# NixieFriday.net
KiCad netlist of a schematic drawn in Altium Designer
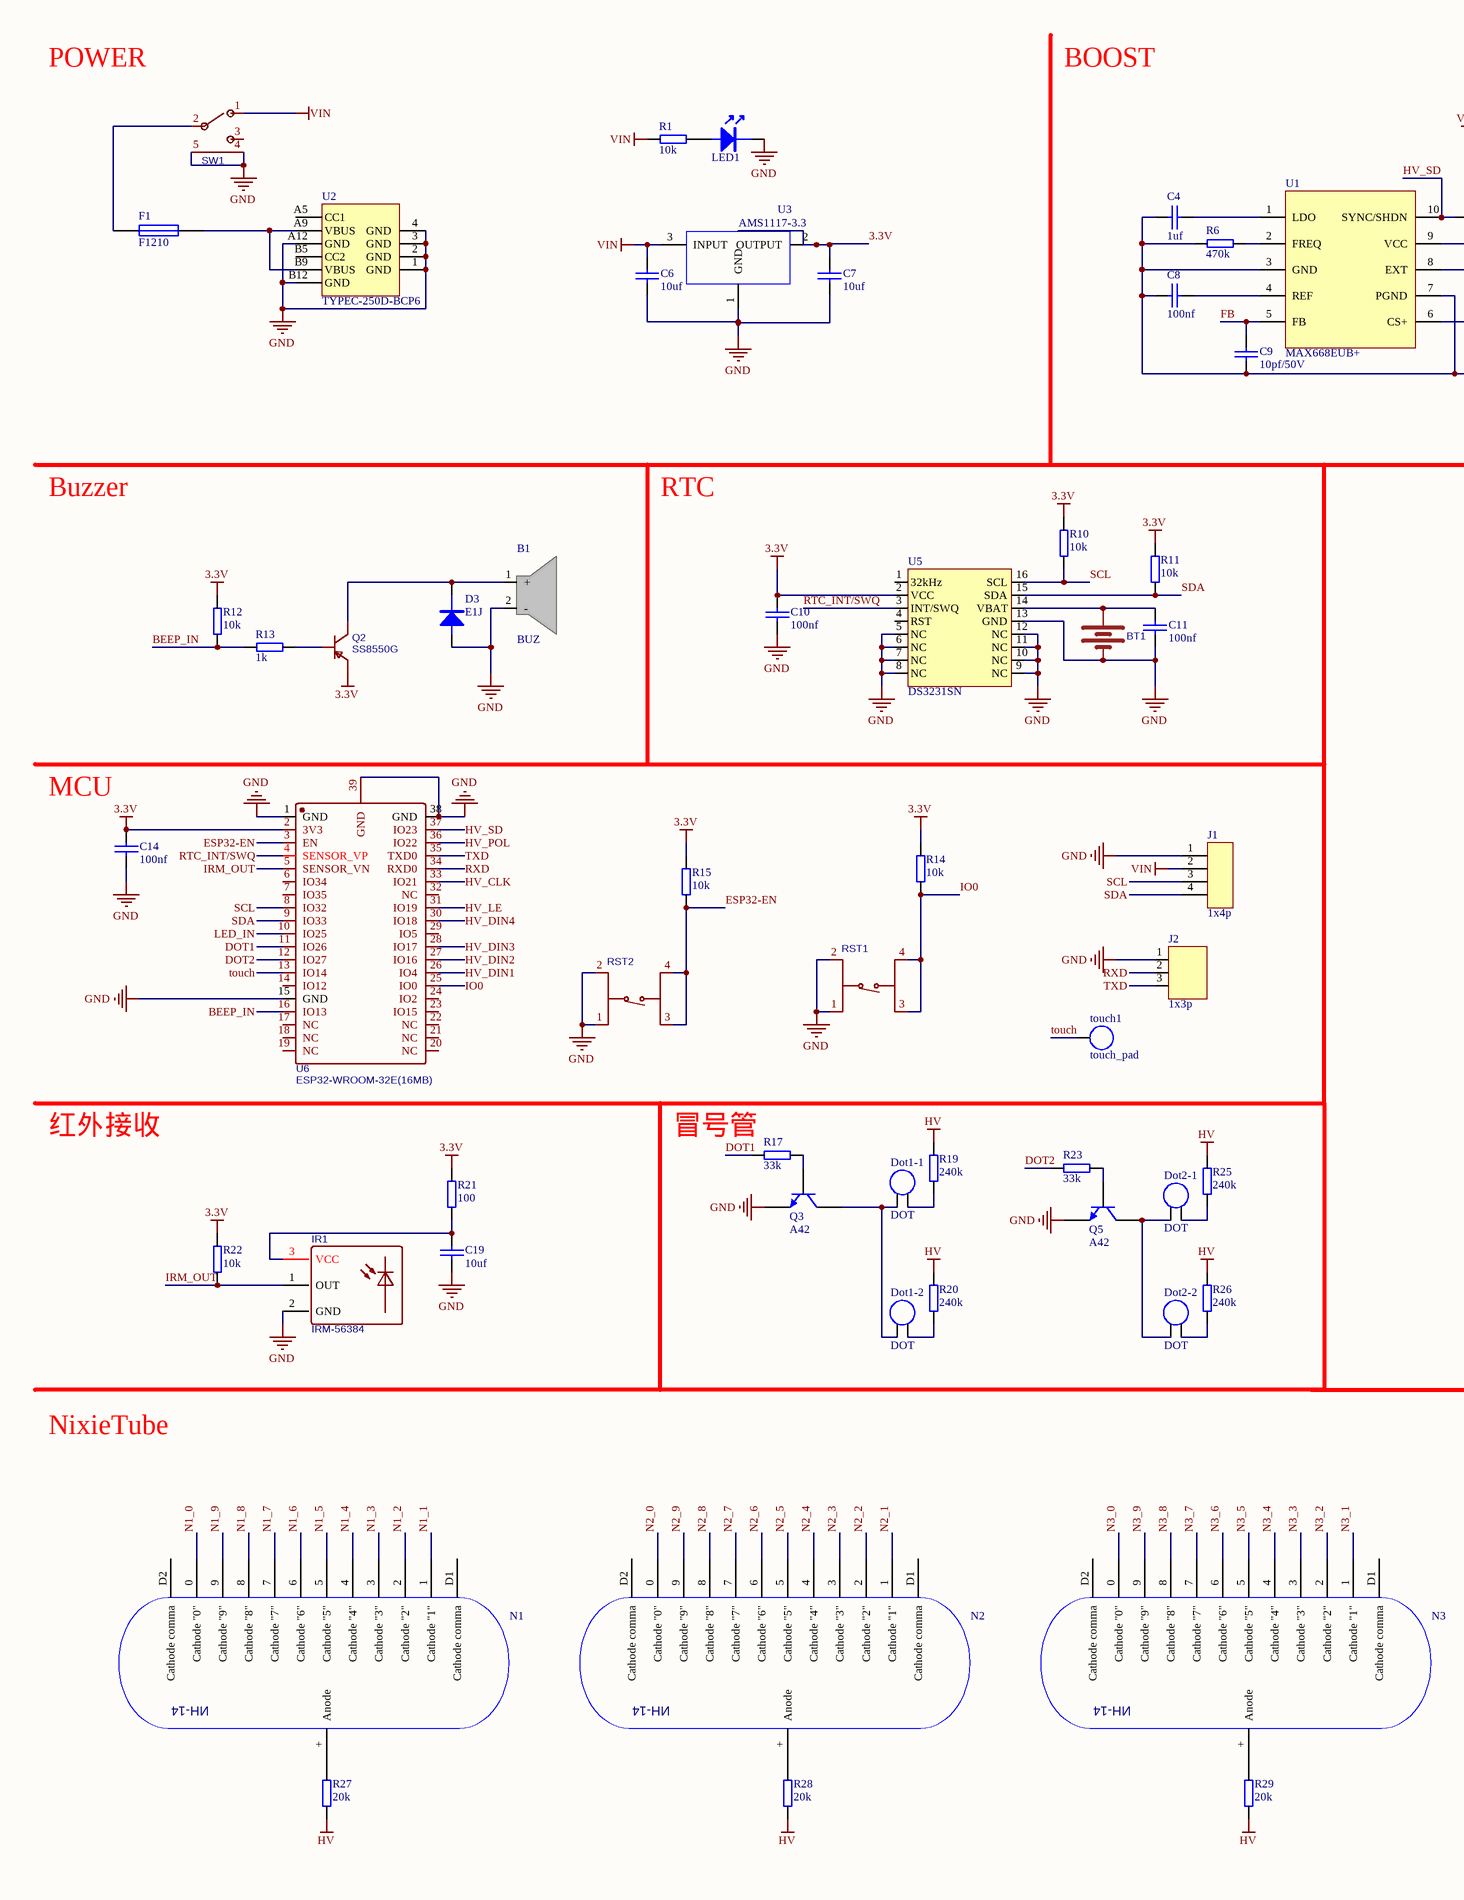
[diagram p0: NixieFriday.SchDoc, left]
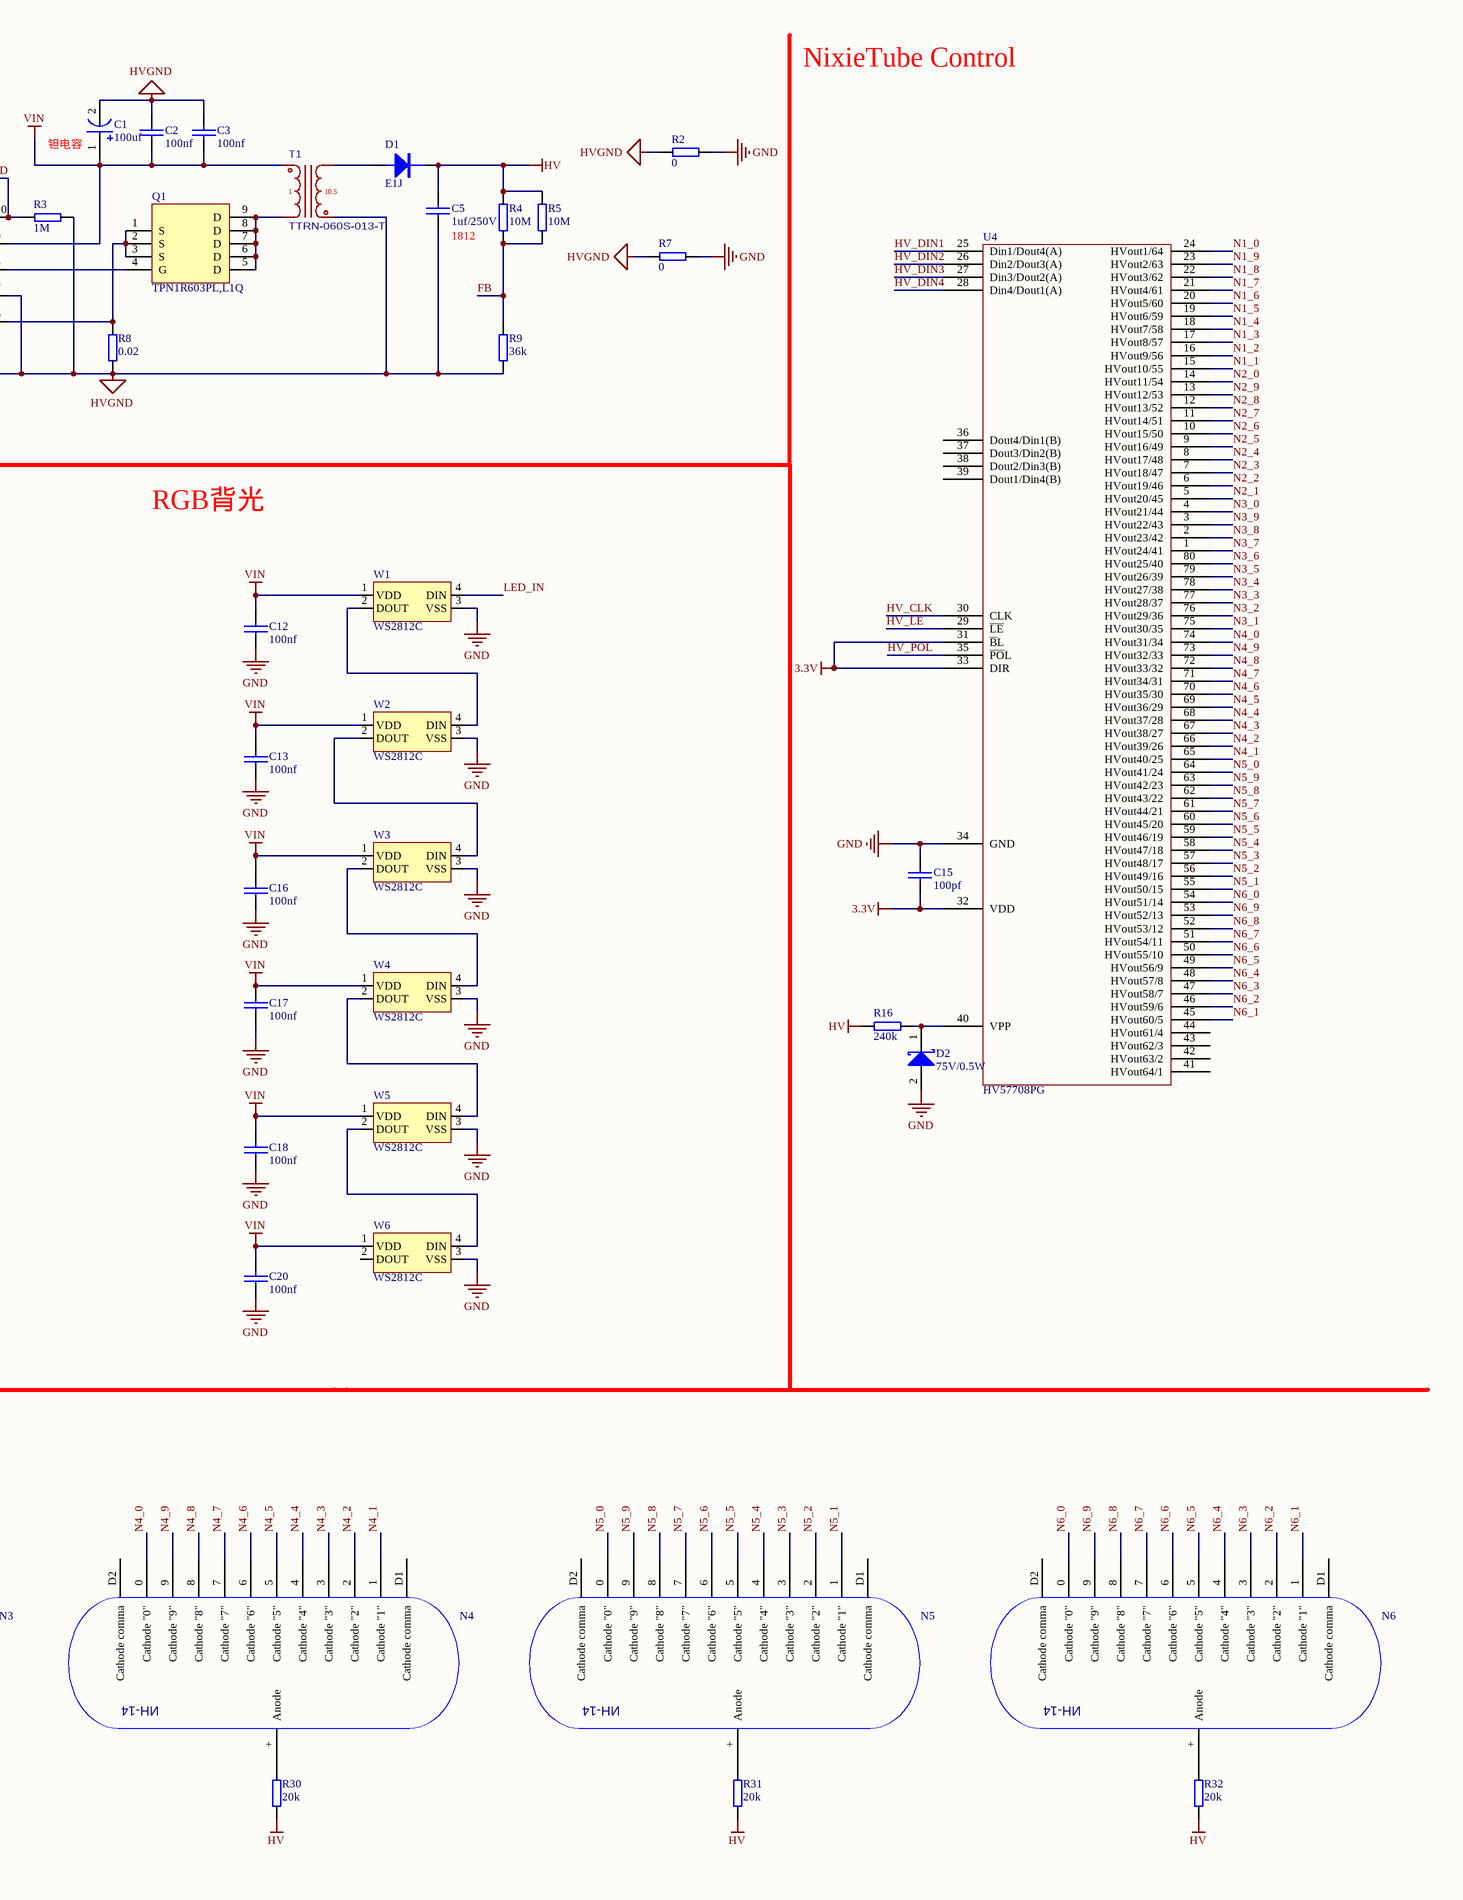
[diagram p1: NixieFriday.SchDoc, right]

(export (version "E")
  (design (tool "Eeschema 10.0.6"))
  (components
    (comp (ref "B1")
      (value "BUZ")
      (footprint "BUZ-SMD_4P-L8.5-W8.5-TL")
      (description "蜂鸣器")
      (libsource (lib "NixieFriday") (part "BUZ"))
    )
    (comp (ref "BT1")
      (value "BS-12-B3AA003")
      (footprint "BAT-SMD_BS-12-B3AA011")
      (description "纽扣电池")
      (fields (field (name "BOM_SUPPLIER PART") "C964723") (field (name "CONTRIBUTOR") "LCSC"))
      (libsource (lib "NixieFriday") (part "BS-12-B3AA003"))
    )
    (comp (ref "C1")
      (value "100uf")
      (footprint "CAP-SMD_L3.2-W1.6-RD")
      (description "极性电容")
      (libsource (lib "NixieFriday") (part "Cap_pol"))
    )
    (comp (ref "C2")
      (value "100nf")
      (footprint "C0603")
      (description "电容")
      (libsource (lib "NixieFriday") (part "Cap"))
    )
    (comp (ref "C3")
      (value "100nf")
      (footprint "C0603")
      (description "电容")
      (libsource (lib "NixieFriday") (part "Cap"))
    )
    (comp (ref "C4")
      (value "1uf")
      (footprint "C0603")
      (description "电容")
      (libsource (lib "NixieFriday") (part "Cap"))
    )
    (comp (ref "C5")
      (value "1uf/250V")
      (footprint "C1812")
      (description "电容")
      (libsource (lib "NixieFriday") (part "Cap"))
    )
    (comp (ref "C6")
      (value "10uf")
      (footprint "C0603")
      (description "电容")
      (libsource (lib "NixieFriday") (part "Cap"))
    )
    (comp (ref "C7")
      (value "10uf")
      (footprint "C0603")
      (description "电容")
      (libsource (lib "NixieFriday") (part "Cap"))
    )
    (comp (ref "C8")
      (value "100nf")
      (footprint "C0603")
      (description "电容")
      (libsource (lib "NixieFriday") (part "Cap"))
    )
    (comp (ref "C9")
      (value "10pf/50V")
      (footprint "C0603")
      (description "电容")
      (libsource (lib "NixieFriday") (part "Cap"))
    )
    (comp (ref "C10")
      (value "100nf")
      (footprint "C0603")
      (description "电容")
      (libsource (lib "NixieFriday") (part "Cap"))
    )
    (comp (ref "C11")
      (value "100nf")
      (footprint "C0603")
      (description "电容")
      (libsource (lib "NixieFriday") (part "Cap"))
    )
    (comp (ref "C12")
      (value "100nf")
      (footprint "C0603")
      (description "电容")
      (libsource (lib "NixieFriday") (part "Cap"))
    )
    (comp (ref "C13")
      (value "100nf")
      (footprint "C0603")
      (description "电容")
      (libsource (lib "NixieFriday") (part "Cap"))
    )
    (comp (ref "C14")
      (value "100nf")
      (footprint "C0603")
      (description "电容")
      (libsource (lib "NixieFriday") (part "Cap"))
    )
    (comp (ref "C15")
      (value "100pf")
      (footprint "C0603")
      (description "电容")
      (libsource (lib "NixieFriday") (part "Cap"))
    )
    (comp (ref "C16")
      (value "100nf")
      (footprint "C0603")
      (description "电容")
      (libsource (lib "NixieFriday") (part "Cap"))
    )
    (comp (ref "C17")
      (value "100nf")
      (footprint "C0603")
      (description "电容")
      (libsource (lib "NixieFriday") (part "Cap"))
    )
    (comp (ref "C18")
      (value "100nf")
      (footprint "C0603")
      (description "电容")
      (libsource (lib "NixieFriday") (part "Cap"))
    )
    (comp (ref "C19")
      (value "10uf")
      (footprint "C0603")
      (description "电容")
      (libsource (lib "NixieFriday") (part "Cap"))
    )
    (comp (ref "C20")
      (value "100nf")
      (footprint "C0603")
      (description "电容")
      (libsource (lib "NixieFriday") (part "Cap"))
    )
    (comp (ref "D1")
      (value "E1J")
      (footprint "SOD-123FL_L2.7-W1.8-LS3.8-RD")
      (libsource (lib "NixieFriday") (part "E1J"))
    )
    (comp (ref "D2")
      (value "75V/0.5W")
      (footprint "75V二极管")
      (description "Schottky Rectifier")
      (fields (field (name "PUBLISHER") "Altium Limited"))
      (libsource (lib "NixieFriday") (part "Diode 10TQ040"))
    )
    (comp (ref "D3")
      (value "E1J")
      (footprint "SOD-123FL_L2.7-W1.8-LS3.8-RD")
      (libsource (lib "NixieFriday") (part "E1J"))
    )
    (comp (ref "Dot1-1")
      (value "DOT")
      (footprint "Neon")
      (description "4x10mm氖泡")
      (libsource (lib "NixieFriday") (part "DOT"))
    )
    (comp (ref "Dot1-2")
      (value "DOT")
      (footprint "Neon")
      (description "4x10mm氖泡")
      (libsource (lib "NixieFriday") (part "DOT"))
    )
    (comp (ref "Dot2-1")
      (value "DOT")
      (footprint "Neon")
      (description "4x10mm氖泡")
      (libsource (lib "NixieFriday") (part "DOT"))
    )
    (comp (ref "Dot2-2")
      (value "DOT")
      (footprint "Neon")
      (description "4x10mm氖泡")
      (libsource (lib "NixieFriday") (part "DOT"))
    )
    (comp (ref "F1")
      (value "F1210")
      (footprint "F1210")
      (fields (field (name "PUBLISHER") "Altium Limited"))
      (libsource (lib "NixieFriday") (part "F1210"))
    )
    (comp (ref "IR1")
      (value "IRM-56384")
      (footprint "OPTO-TH_IRM-56384")
      (description "红外接收管")
      (fields (field (name "BOM_SUPPLIER PART") "C72048"))
      (libsource (lib "NixieFriday") (part "IRM-56384"))
    )
    (comp (ref "J1")
      (value "1x4p")
      (footprint "1x4p_2.54_弯")
      (description "2.54mm")
      (libsource (lib "NixieFriday") (part "1x4p"))
    )
    (comp (ref "J2") (value "1x3p") (footprint "1x3p") (libsource (lib "NixieFriday") (part "1x3p")))
    (comp (ref "LED1")
      (value "LED")
      (footprint "LED0603")
      (description "LED发光管")
      (libsource (lib "pwoer_test") (part "LED"))
    )
    (comp (ref "N1") (value "ИН-14") (footprint "NH_14_PIN") (libsource (lib "NixieFriday") (part "ИН-14")))
    (comp (ref "N2") (value "ИН-14") (footprint "NH_14_PIN") (libsource (lib "NixieFriday") (part "ИН-14")))
    (comp (ref "N3") (value "ИН-14") (footprint "NH_14_PIN") (libsource (lib "NixieFriday") (part "ИН-14")))
    (comp (ref "N4") (value "ИН-14") (footprint "NH_14_PIN") (libsource (lib "NixieFriday") (part "ИН-14")))
    (comp (ref "N5") (value "ИН-14") (footprint "NH_14_PIN") (libsource (lib "NixieFriday") (part "ИН-14")))
    (comp (ref "N6") (value "ИН-14") (footprint "NH_14_PIN") (libsource (lib "NixieFriday") (part "ИН-14")))
    (comp (ref "Q1")
      (value "TPN1R603PL,L1Q")
      (footprint "PG-TSDSON-8_L3.3-W3.3-P0.65-BL")
      (libsource (lib "NixieFriday") (part "TPN1R603PL,L1Q"))
    )
    (comp (ref "Q2")
      (value "SS8550G")
      (footprint "ss8550g")
      (fields (field (name "BOM_SUPPLIER PART") "C380931") (field (name "CONTRIBUTOR") "LCSC"))
      (libsource (lib "NixieFriday") (part "SS8550G"))
    )
    (comp (ref "Q3")
      (value "A42")
      (footprint "SOT-23-3")
      (description "NPN General Purpose Amplifier")
      (fields (field (name "PUBLISHER") "Altium Limited"))
      (libsource (lib "NixieFriday") (part "2N3904"))
    )
    (comp (ref "Q5")
      (value "A42")
      (footprint "SOT-23-3")
      (description "NPN General Purpose Amplifier")
      (fields (field (name "PUBLISHER") "Altium Limited"))
      (libsource (lib "NixieFriday") (part "2N3904"))
    )
    (comp (ref "R1")
      (value "10k")
      (footprint "R0603")
      (description "电阻")
      (libsource (lib "NixieFriday") (part "R"))
    )
    (comp (ref "R2")
      (value "0")
      (footprint "R0805")
      (description "电阻")
      (libsource (lib "NixieFriday") (part "R"))
    )
    (comp (ref "R3")
      (value "1M")
      (footprint "R0603")
      (description "电阻")
      (libsource (lib "NixieFriday") (part "R"))
    )
    (comp (ref "R4")
      (value "10M")
      (footprint "R0805")
      (description "电阻")
      (libsource (lib "NixieFriday") (part "R"))
    )
    (comp (ref "R5")
      (value "10M")
      (footprint "R0805")
      (description "电阻")
      (libsource (lib "NixieFriday") (part "R"))
    )
    (comp (ref "R6")
      (value "470k")
      (footprint "R0603")
      (description "电阻")
      (libsource (lib "NixieFriday") (part "R"))
    )
    (comp (ref "R7")
      (value "0")
      (footprint "R0805")
      (description "电阻")
      (libsource (lib "NixieFriday") (part "R"))
    )
    (comp (ref "R8")
      (value "0.02")
      (footprint "R0805")
      (description "电阻")
      (libsource (lib "NixieFriday") (part "R"))
    )
    (comp (ref "R9")
      (value "36k")
      (footprint "R0805")
      (description "电阻")
      (libsource (lib "NixieFriday") (part "R"))
    )
    (comp (ref "R10")
      (value "10k")
      (footprint "R0603")
      (description "电阻")
      (libsource (lib "NixieFriday") (part "R"))
    )
    (comp (ref "R11")
      (value "10k")
      (footprint "R0603")
      (description "电阻")
      (libsource (lib "NixieFriday") (part "R"))
    )
    (comp (ref "R12")
      (value "10k")
      (footprint "R0603")
      (description "电阻")
      (libsource (lib "NixieFriday") (part "R"))
    )
    (comp (ref "R13")
      (value "1k")
      (footprint "R0603")
      (description "电阻")
      (libsource (lib "NixieFriday") (part "R"))
    )
    (comp (ref "R14")
      (value "10k")
      (footprint "R0603")
      (description "电阻")
      (libsource (lib "NixieFriday") (part "R"))
    )
    (comp (ref "R15")
      (value "10k")
      (footprint "R0603")
      (description "电阻")
      (libsource (lib "NixieFriday") (part "R"))
    )
    (comp (ref "R16")
      (value "240k")
      (footprint "R0805")
      (description "电阻")
      (libsource (lib "NixieFriday") (part "R"))
    )
    (comp (ref "R17")
      (value "33k")
      (footprint "R0603")
      (description "电阻")
      (libsource (lib "NixieFriday") (part "R"))
    )
    (comp (ref "R19")
      (value "240k")
      (footprint "R0805")
      (description "电阻")
      (libsource (lib "NixieFriday") (part "R"))
    )
    (comp (ref "R20")
      (value "240k")
      (footprint "R0805")
      (description "电阻")
      (libsource (lib "NixieFriday") (part "R"))
    )
    (comp (ref "R21")
      (value "100")
      (footprint "R0603")
      (description "电阻")
      (libsource (lib "NixieFriday") (part "R"))
    )
    (comp (ref "R22")
      (value "10k")
      (footprint "R0603")
      (description "电阻")
      (libsource (lib "NixieFriday") (part "R"))
    )
    (comp (ref "R23")
      (value "33k")
      (footprint "R0603")
      (description "电阻")
      (libsource (lib "NixieFriday") (part "R"))
    )
    (comp (ref "R25")
      (value "240k")
      (footprint "R0805")
      (description "电阻")
      (libsource (lib "NixieFriday") (part "R"))
    )
    (comp (ref "R26")
      (value "240k")
      (footprint "R0805")
      (description "电阻")
      (libsource (lib "NixieFriday") (part "R"))
    )
    (comp (ref "R27")
      (value "20k")
      (footprint "R0805")
      (description "电阻")
      (libsource (lib "NixieFriday") (part "R"))
    )
    (comp (ref "R28")
      (value "20k")
      (footprint "R0805")
      (description "电阻")
      (libsource (lib "NixieFriday") (part "R"))
    )
    (comp (ref "R29")
      (value "20k")
      (footprint "R0805")
      (description "电阻")
      (libsource (lib "NixieFriday") (part "R"))
    )
    (comp (ref "R30")
      (value "20k")
      (footprint "R0805")
      (description "电阻")
      (libsource (lib "NixieFriday") (part "R"))
    )
    (comp (ref "R31")
      (value "20k")
      (footprint "R0805")
      (description "电阻")
      (libsource (lib "NixieFriday") (part "R"))
    )
    (comp (ref "R32")
      (value "20k")
      (footprint "R0805")
      (description "电阻")
      (libsource (lib "NixieFriday") (part "R"))
    )
    (comp (ref "RST1")
      (value "1TS001G-1500-1700")
      (footprint "SW-SMD_4P-L5.1-W5.1-P3.70-LS6.5-TL-2")
      (fields (field (name "BOM_SUPPLIER PART") "C318801") (field (name "CONTRIBUTOR") "LCSC"))
      (libsource (lib "NixieFriday") (part "1TS001G-1500-1700"))
    )
    (comp (ref "RST2")
      (value "1TS001G-1500-1700")
      (footprint "SW-SMD_4P-L5.1-W5.1-P3.70-LS6.5-TL-2")
      (fields (field (name "BOM_SUPPLIER PART") "C318801") (field (name "CONTRIBUTOR") "LCSC"))
      (libsource (lib "NixieFriday") (part "1TS001G-1500-1700"))
    )
    (comp (ref "SW1")
      (value "ST-0-102-C03-N003-RS")
      (footprint "钮子开关")
      (fields (field (name "BOM_SUPPLIER PART") "C1788489") (field (name "CONTRIBUTOR") "LCSC"))
      (libsource (lib "NixieFriday") (part "钮子开关"))
    )
    (comp (ref "T1")
      (value "TTRN-060S-013-T")
      (footprint "TTRN-060S-013")
      (libsource (lib "NixieFriday") (part "TTRN-060S-013-T"))
    )
    (comp (ref "touch1")
      (value "touch_pad")
      (footprint "touch_pad")
      (libsource (lib "NixieFriday") (part "touch_pad"))
    )
    (comp (ref "U1")
      (value "MAX668EUB+")
      (footprint "MAX668_MSOP-10")
      (libsource (lib "NixieFriday") (part "MAX668EUB+"))
    )
    (comp (ref "U2")
      (value "TYPEC-250D-BCP6")
      (footprint "USB-C-SMD_TYPEC-250D-BCP6")
      (description "TypeC母座")
      (libsource (lib "NixieFriday") (part "TYPEC-250D-BCP6"))
    )
    (comp (ref "U3")
      (value "AMS1117-3.3")
      (footprint "SOT-223")
      (libsource (lib "NixieFriday") (part "AMS1117-3.3"))
    )
    (comp (ref "U4")
      (value "HV57708PG")
      (footprint "PQFP80")
      (libsource (lib "NixieFriday") (part "HV57708PG"))
    )
    (comp (ref "U5")
      (value "DS3231SN")
      (footprint "DS3231_SOIC-16")
      (description "RTC芯片")
      (libsource (lib "NixieFriday") (part "DS3231SN"))
    )
    (comp (ref "U6")
      (value "ESP32-WROOM-32E(16MB)")
      (footprint "WIFI-SMD_ESP32-WROOM-32E")
      (fields (field (name "BOM_SUPPLIER PART") "C701343") (field (name "CONTRIBUTOR") "LCSC"))
      (libsource (lib "NixieFriday") (part "ESP32-WROOM-32E(16MB)"))
    )
    (comp (ref "W1")
      (value "WS2812C")
      (footprint "LED-SMD_4P-L5.0-W5.0-TL_WS2812B-B")
      (libsource (lib "NixieFriday") (part "WS2812C"))
    )
    (comp (ref "W2")
      (value "WS2812C")
      (footprint "LED-SMD_4P-L5.0-W5.0-TL_WS2812B-B")
      (libsource (lib "NixieFriday") (part "WS2812C"))
    )
    (comp (ref "W3")
      (value "WS2812C")
      (footprint "LED-SMD_4P-L5.0-W5.0-TL_WS2812B-B")
      (libsource (lib "NixieFriday") (part "WS2812C"))
    )
    (comp (ref "W4")
      (value "WS2812C")
      (footprint "LED-SMD_4P-L5.0-W5.0-TL_WS2812B-B")
      (libsource (lib "NixieFriday") (part "WS2812C"))
    )
    (comp (ref "W5")
      (value "WS2812C")
      (footprint "LED-SMD_4P-L5.0-W5.0-TL_WS2812B-B")
      (libsource (lib "NixieFriday") (part "WS2812C"))
    )
    (comp (ref "W6")
      (value "WS2812C")
      (footprint "LED-SMD_4P-L5.0-W5.0-TL_WS2812B-B")
      (libsource (lib "NixieFriday") (part "WS2812C"))
    )
  )
  (nets
    (net (code "1") (name "/BEEP_IN") (class "Default")
      (node (ref "R12") (pin "1") (pinfunction "1_1") (pintype "passive"))
      (node (ref "R13") (pin "2") (pinfunction "2_2") (pintype "passive"))
      (node (ref "U6") (pin "16") (pinfunction "IO13_16") (pintype "passive"))
    )
    (net (code "2") (name "/DOT1") (class "Default")
      (node (ref "R17") (pin "2") (pinfunction "2_2") (pintype "passive"))
      (node (ref "U6") (pin "11") (pinfunction "IO26_11") (pintype "passive"))
    )
    (net (code "3") (name "/DOT2") (class "Default")
      (node (ref "R23") (pin "2") (pinfunction "2_2") (pintype "passive"))
      (node (ref "U6") (pin "12") (pinfunction "IO27_12") (pintype "passive"))
    )
    (net (code "4") (name "/ESP32-EN") (class "Default")
      (node (ref "R15") (pin "1") (pinfunction "1_1") (pintype "passive"))
      (node (ref "RST2") (pin "3") (pinfunction "C_3") (pintype "passive"))
      (node (ref "RST2") (pin "4") (pinfunction "D_4") (pintype "passive"))
      (node (ref "U6") (pin "3") (pinfunction "EN_3") (pintype "passive"))
    )
    (net (code "5") (name "/FB") (class "Default")
      (node (ref "C9") (pin "1") (pinfunction "1_1") (pintype "passive"))
      (node (ref "R4") (pin "1") (pinfunction "1_1") (pintype "passive"))
      (node (ref "R5") (pin "1") (pinfunction "1_1") (pintype "passive"))
      (node (ref "R9") (pin "2") (pinfunction "2_2") (pintype "passive"))
      (node (ref "U1") (pin "5") (pinfunction "FB_5") (pintype "passive"))
    )
    (net (code "6") (name "/HV_CLK") (class "Default")
      (node (ref "U4") (pin "30") (pinfunction "CLK_30") (pintype "passive"))
      (node (ref "U6") (pin "33") (pinfunction "IO21_33") (pintype "passive"))
    )
    (net (code "7") (name "/HV_DIN1") (class "Default")
      (node (ref "U4") (pin "25") (pinfunction "Din1/Dout4(A)_25") (pintype "passive"))
      (node (ref "U6") (pin "26") (pinfunction "IO4_26") (pintype "passive"))
    )
    (net (code "8") (name "/HV_DIN2") (class "Default")
      (node (ref "U4") (pin "26") (pinfunction "Din2/Dout3(A)_26") (pintype "passive"))
      (node (ref "U6") (pin "27") (pinfunction "IO16_27") (pintype "passive"))
    )
    (net (code "9") (name "/HV_DIN3") (class "Default")
      (node (ref "U4") (pin "27") (pinfunction "Din3/Dout2(A)_27") (pintype "passive"))
      (node (ref "U6") (pin "28") (pinfunction "IO17_28") (pintype "passive"))
    )
    (net (code "10") (name "/HV_DIN4") (class "Default")
      (node (ref "U4") (pin "28") (pinfunction "Din4/Dout1(A)_28") (pintype "passive"))
      (node (ref "U6") (pin "30") (pinfunction "IO18_30") (pintype "passive"))
    )
    (net (code "11") (name "/HV_LE") (class "Default")
      (node (ref "U4") (pin "29") (pinfunction "~{LE}_29") (pintype "passive"))
      (node (ref "U6") (pin "31") (pinfunction "IO19_31") (pintype "passive"))
    )
    (net (code "12") (name "/HV_POL") (class "Default")
      (node (ref "U4") (pin "35") (pinfunction "~{PO}L_35") (pintype "passive"))
      (node (ref "U6") (pin "36") (pinfunction "IO22_36") (pintype "passive"))
    )
    (net (code "13") (name "/HV_SD") (class "Default")
      (node (ref "R3") (pin "2") (pinfunction "2_2") (pintype "passive"))
      (node (ref "U1") (pin "10") (pinfunction "SYNC/SHDN_10") (pintype "passive"))
      (node (ref "U6") (pin "37") (pinfunction "IO23_37") (pintype "passive"))
    )
    (net (code "14") (name "/IO0") (class "Default")
      (node (ref "R14") (pin "1") (pinfunction "1_1") (pintype "passive"))
      (node (ref "RST1") (pin "3") (pinfunction "C_3") (pintype "passive"))
      (node (ref "RST1") (pin "4") (pinfunction "D_4") (pintype "passive"))
      (node (ref "U6") (pin "25") (pinfunction "IO0_25") (pintype "passive"))
    )
    (net (code "15") (name "/IRM_OUT") (class "Default")
      (node (ref "IR1") (pin "1") (pinfunction "OUT_1") (pintype "passive"))
      (node (ref "R22") (pin "1") (pinfunction "1_1") (pintype "passive"))
      (node (ref "U6") (pin "5") (pinfunction "SENSOR_VN_5") (pintype "passive"))
    )
    (net (code "16") (name "/LED_IN") (class "Default")
      (node (ref "U6") (pin "10") (pinfunction "IO25_10") (pintype "passive"))
      (node (ref "W1") (pin "4") (pinfunction "DIN_4") (pintype "passive"))
    )
    (net (code "17") (name "/N1_0") (class "Default")
      (node (ref "N1") (pin "0") (pinfunction "Cathode_\"0\"_0") (pintype "passive"))
      (node (ref "U4") (pin "24") (pinfunction "HVout1/64_24") (pintype "passive"))
    )
    (net (code "18") (name "/N1_1") (class "Default")
      (node (ref "N1") (pin "1") (pinfunction "Cathode_\"1\"_1") (pintype "passive"))
      (node (ref "U4") (pin "15") (pinfunction "HVout10/55_15") (pintype "passive"))
    )
    (net (code "19") (name "/N1_2") (class "Default")
      (node (ref "N1") (pin "2") (pinfunction "Cathode_\"2\"_2") (pintype "passive"))
      (node (ref "U4") (pin "16") (pinfunction "HVout9/56_16") (pintype "passive"))
    )
    (net (code "20") (name "/N1_3") (class "Default")
      (node (ref "N1") (pin "3") (pinfunction "Cathode_\"3\"_3") (pintype "passive"))
      (node (ref "U4") (pin "17") (pinfunction "HVout8/57_17") (pintype "passive"))
    )
    (net (code "21") (name "/N1_4") (class "Default")
      (node (ref "N1") (pin "4") (pinfunction "Cathode_\"4\"_4") (pintype "passive"))
      (node (ref "U4") (pin "18") (pinfunction "HVout7/58_18") (pintype "passive"))
    )
    (net (code "22") (name "/N1_5") (class "Default")
      (node (ref "N1") (pin "5") (pinfunction "Cathode_\"5\"_5") (pintype "passive"))
      (node (ref "U4") (pin "19") (pinfunction "HVout6/59_19") (pintype "passive"))
    )
    (net (code "23") (name "/N1_6") (class "Default")
      (node (ref "N1") (pin "6") (pinfunction "Cathode_\"6\"_6") (pintype "passive"))
      (node (ref "U4") (pin "20") (pinfunction "HVout5/60_20") (pintype "passive"))
    )
    (net (code "24") (name "/N1_7") (class "Default")
      (node (ref "N1") (pin "7") (pinfunction "Cathode_\"7\"_7") (pintype "passive"))
      (node (ref "U4") (pin "21") (pinfunction "HVout4/61_21") (pintype "passive"))
    )
    (net (code "25") (name "/N1_8") (class "Default")
      (node (ref "N1") (pin "8") (pinfunction "Cathode_\"8\"_8") (pintype "passive"))
      (node (ref "U4") (pin "22") (pinfunction "HVout3/62_22") (pintype "passive"))
    )
    (net (code "26") (name "/N1_9") (class "Default")
      (node (ref "N1") (pin "9") (pinfunction "Cathode_\"9\"_9") (pintype "passive"))
      (node (ref "U4") (pin "23") (pinfunction "HVout2/63_23") (pintype "passive"))
    )
    (net (code "27") (name "/N2_0") (class "Default")
      (node (ref "N2") (pin "0") (pinfunction "Cathode_\"0\"_0") (pintype "passive"))
      (node (ref "U4") (pin "14") (pinfunction "HVout11/54_14") (pintype "passive"))
    )
    (net (code "28") (name "/N2_1") (class "Default")
      (node (ref "N2") (pin "1") (pinfunction "Cathode_\"1\"_1") (pintype "passive"))
      (node (ref "U4") (pin "5") (pinfunction "HVout20/45_5") (pintype "passive"))
    )
    (net (code "29") (name "/N2_2") (class "Default")
      (node (ref "N2") (pin "2") (pinfunction "Cathode_\"2\"_2") (pintype "passive"))
      (node (ref "U4") (pin "6") (pinfunction "HVout19/46_6") (pintype "passive"))
    )
    (net (code "30") (name "/N2_3") (class "Default")
      (node (ref "N2") (pin "3") (pinfunction "Cathode_\"3\"_3") (pintype "passive"))
      (node (ref "U4") (pin "7") (pinfunction "HVout18/47_7") (pintype "passive"))
    )
    (net (code "31") (name "/N2_4") (class "Default")
      (node (ref "N2") (pin "4") (pinfunction "Cathode_\"4\"_4") (pintype "passive"))
      (node (ref "U4") (pin "8") (pinfunction "HVout17/48_8") (pintype "passive"))
    )
    (net (code "32") (name "/N2_5") (class "Default")
      (node (ref "N2") (pin "5") (pinfunction "Cathode_\"5\"_5") (pintype "passive"))
      (node (ref "U4") (pin "9") (pinfunction "HVout16/49_9") (pintype "passive"))
    )
    (net (code "33") (name "/N2_6") (class "Default")
      (node (ref "N2") (pin "6") (pinfunction "Cathode_\"6\"_6") (pintype "passive"))
      (node (ref "U4") (pin "10") (pinfunction "HVout15/50_10") (pintype "passive"))
    )
    (net (code "34") (name "/N2_7") (class "Default")
      (node (ref "N2") (pin "7") (pinfunction "Cathode_\"7\"_7") (pintype "passive"))
      (node (ref "U4") (pin "11") (pinfunction "HVout14/51_11") (pintype "passive"))
    )
    (net (code "35") (name "/N2_8") (class "Default")
      (node (ref "N2") (pin "8") (pinfunction "Cathode_\"8\"_8") (pintype "passive"))
      (node (ref "U4") (pin "12") (pinfunction "HVout13/52_12") (pintype "passive"))
    )
    (net (code "36") (name "/N2_9") (class "Default")
      (node (ref "N2") (pin "9") (pinfunction "Cathode_\"9\"_9") (pintype "passive"))
      (node (ref "U4") (pin "13") (pinfunction "HVout12/53_13") (pintype "passive"))
    )
    (net (code "37") (name "/N3_0") (class "Default")
      (node (ref "N3") (pin "0") (pinfunction "Cathode_\"0\"_0") (pintype "passive"))
      (node (ref "U4") (pin "4") (pinfunction "HVout21/44_4") (pintype "passive"))
    )
    (net (code "38") (name "/N3_1") (class "Default")
      (node (ref "N3") (pin "1") (pinfunction "Cathode_\"1\"_1") (pintype "passive"))
      (node (ref "U4") (pin "75") (pinfunction "HVout30/35_75") (pintype "passive"))
    )
    (net (code "39") (name "/N3_2") (class "Default")
      (node (ref "N3") (pin "2") (pinfunction "Cathode_\"2\"_2") (pintype "passive"))
      (node (ref "U4") (pin "76") (pinfunction "HVout29/36_76") (pintype "passive"))
    )
    (net (code "40") (name "/N3_3") (class "Default")
      (node (ref "N3") (pin "3") (pinfunction "Cathode_\"3\"_3") (pintype "passive"))
      (node (ref "U4") (pin "77") (pinfunction "HVout28/37_77") (pintype "passive"))
    )
    (net (code "41") (name "/N3_4") (class "Default")
      (node (ref "N3") (pin "4") (pinfunction "Cathode_\"4\"_4") (pintype "passive"))
      (node (ref "U4") (pin "78") (pinfunction "HVout27/38_78") (pintype "passive"))
    )
    (net (code "42") (name "/N3_5") (class "Default")
      (node (ref "N3") (pin "5") (pinfunction "Cathode_\"5\"_5") (pintype "passive"))
      (node (ref "U4") (pin "79") (pinfunction "HVout26/39_79") (pintype "passive"))
    )
    (net (code "43") (name "/N3_6") (class "Default")
      (node (ref "N3") (pin "6") (pinfunction "Cathode_\"6\"_6") (pintype "passive"))
      (node (ref "U4") (pin "80") (pinfunction "HVout25/40_80") (pintype "passive"))
    )
    (net (code "44") (name "/N3_7") (class "Default")
      (node (ref "N3") (pin "7") (pinfunction "Cathode_\"7\"_7") (pintype "passive"))
      (node (ref "U4") (pin "1") (pinfunction "HVout24/41_1") (pintype "passive"))
    )
    (net (code "45") (name "/N3_8") (class "Default")
      (node (ref "N3") (pin "8") (pinfunction "Cathode_\"8\"_8") (pintype "passive"))
      (node (ref "U4") (pin "2") (pinfunction "HVout23/42_2") (pintype "passive"))
    )
    (net (code "46") (name "/N3_9") (class "Default")
      (node (ref "N3") (pin "9") (pinfunction "Cathode_\"9\"_9") (pintype "passive"))
      (node (ref "U4") (pin "3") (pinfunction "HVout22/43_3") (pintype "passive"))
    )
    (net (code "47") (name "/N4_0") (class "Default")
      (node (ref "N4") (pin "0") (pinfunction "Cathode_\"0\"_0") (pintype "passive"))
      (node (ref "U4") (pin "74") (pinfunction "HVout31/34_74") (pintype "passive"))
    )
    (net (code "48") (name "/N4_1") (class "Default")
      (node (ref "N4") (pin "1") (pinfunction "Cathode_\"1\"_1") (pintype "passive"))
      (node (ref "U4") (pin "65") (pinfunction "HVout40/25_65") (pintype "passive"))
    )
    (net (code "49") (name "/N4_2") (class "Default")
      (node (ref "N4") (pin "2") (pinfunction "Cathode_\"2\"_2") (pintype "passive"))
      (node (ref "U4") (pin "66") (pinfunction "HVout39/26_66") (pintype "passive"))
    )
    (net (code "50") (name "/N4_3") (class "Default")
      (node (ref "N4") (pin "3") (pinfunction "Cathode_\"3\"_3") (pintype "passive"))
      (node (ref "U4") (pin "67") (pinfunction "HVout38/27_67") (pintype "passive"))
    )
    (net (code "51") (name "/N4_4") (class "Default")
      (node (ref "N4") (pin "4") (pinfunction "Cathode_\"4\"_4") (pintype "passive"))
      (node (ref "U4") (pin "68") (pinfunction "HVout37/28_68") (pintype "passive"))
    )
    (net (code "52") (name "/N4_5") (class "Default")
      (node (ref "N4") (pin "5") (pinfunction "Cathode_\"5\"_5") (pintype "passive"))
      (node (ref "U4") (pin "69") (pinfunction "HVout36/29_69") (pintype "passive"))
    )
    (net (code "53") (name "/N4_6") (class "Default")
      (node (ref "N4") (pin "6") (pinfunction "Cathode_\"6\"_6") (pintype "passive"))
      (node (ref "U4") (pin "70") (pinfunction "HVout35/30_70") (pintype "passive"))
    )
    (net (code "54") (name "/N4_7") (class "Default")
      (node (ref "N4") (pin "7") (pinfunction "Cathode_\"7\"_7") (pintype "passive"))
      (node (ref "U4") (pin "71") (pinfunction "HVout34/31_71") (pintype "passive"))
    )
    (net (code "55") (name "/N4_8") (class "Default")
      (node (ref "N4") (pin "8") (pinfunction "Cathode_\"8\"_8") (pintype "passive"))
      (node (ref "U4") (pin "72") (pinfunction "HVout33/32_72") (pintype "passive"))
    )
    (net (code "56") (name "/N4_9") (class "Default")
      (node (ref "N4") (pin "9") (pinfunction "Cathode_\"9\"_9") (pintype "passive"))
      (node (ref "U4") (pin "73") (pinfunction "HVout32/33_73") (pintype "passive"))
    )
    (net (code "57") (name "/N5_0") (class "Default")
      (node (ref "N5") (pin "0") (pinfunction "Cathode_\"0\"_0") (pintype "passive"))
      (node (ref "U4") (pin "64") (pinfunction "HVout41/24_64") (pintype "passive"))
    )
    (net (code "58") (name "/N5_1") (class "Default")
      (node (ref "N5") (pin "1") (pinfunction "Cathode_\"1\"_1") (pintype "passive"))
      (node (ref "U4") (pin "55") (pinfunction "HVout50/15_55") (pintype "passive"))
    )
    (net (code "59") (name "/N5_2") (class "Default")
      (node (ref "N5") (pin "2") (pinfunction "Cathode_\"2\"_2") (pintype "passive"))
      (node (ref "U4") (pin "56") (pinfunction "HVout49/16_56") (pintype "passive"))
    )
    (net (code "60") (name "/N5_3") (class "Default")
      (node (ref "N5") (pin "3") (pinfunction "Cathode_\"3\"_3") (pintype "passive"))
      (node (ref "U4") (pin "57") (pinfunction "HVout48/17_57") (pintype "passive"))
    )
    (net (code "61") (name "/N5_4") (class "Default")
      (node (ref "N5") (pin "4") (pinfunction "Cathode_\"4\"_4") (pintype "passive"))
      (node (ref "U4") (pin "58") (pinfunction "HVout47/18_58") (pintype "passive"))
    )
    (net (code "62") (name "/N5_5") (class "Default")
      (node (ref "N5") (pin "5") (pinfunction "Cathode_\"5\"_5") (pintype "passive"))
      (node (ref "U4") (pin "59") (pinfunction "HVout46/19_59") (pintype "passive"))
    )
    (net (code "63") (name "/N5_6") (class "Default")
      (node (ref "N5") (pin "6") (pinfunction "Cathode_\"6\"_6") (pintype "passive"))
      (node (ref "U4") (pin "60") (pinfunction "HVout45/20_60") (pintype "passive"))
    )
    (net (code "64") (name "/N5_7") (class "Default")
      (node (ref "N5") (pin "7") (pinfunction "Cathode_\"7\"_7") (pintype "passive"))
      (node (ref "U4") (pin "61") (pinfunction "HVout44/21_61") (pintype "passive"))
    )
    (net (code "65") (name "/N5_8") (class "Default")
      (node (ref "N5") (pin "8") (pinfunction "Cathode_\"8\"_8") (pintype "passive"))
      (node (ref "U4") (pin "62") (pinfunction "HVout43/22_62") (pintype "passive"))
    )
    (net (code "66") (name "/N5_9") (class "Default")
      (node (ref "N5") (pin "9") (pinfunction "Cathode_\"9\"_9") (pintype "passive"))
      (node (ref "U4") (pin "63") (pinfunction "HVout42/23_63") (pintype "passive"))
    )
    (net (code "67") (name "/N6_0") (class "Default")
      (node (ref "N6") (pin "0") (pinfunction "Cathode_\"0\"_0") (pintype "passive"))
      (node (ref "U4") (pin "54") (pinfunction "HVout51/14_54") (pintype "passive"))
    )
    (net (code "68") (name "/N6_1") (class "Default")
      (node (ref "N6") (pin "1") (pinfunction "Cathode_\"1\"_1") (pintype "passive"))
      (node (ref "U4") (pin "45") (pinfunction "HVout60/5_45") (pintype "passive"))
    )
    (net (code "69") (name "/N6_2") (class "Default")
      (node (ref "N6") (pin "2") (pinfunction "Cathode_\"2\"_2") (pintype "passive"))
      (node (ref "U4") (pin "46") (pinfunction "HVout59/6_46") (pintype "passive"))
    )
    (net (code "70") (name "/N6_3") (class "Default")
      (node (ref "N6") (pin "3") (pinfunction "Cathode_\"3\"_3") (pintype "passive"))
      (node (ref "U4") (pin "47") (pinfunction "HVout58/7_47") (pintype "passive"))
    )
    (net (code "71") (name "/N6_4") (class "Default")
      (node (ref "N6") (pin "4") (pinfunction "Cathode_\"4\"_4") (pintype "passive"))
      (node (ref "U4") (pin "48") (pinfunction "HVout57/8_48") (pintype "passive"))
    )
    (net (code "72") (name "/N6_5") (class "Default")
      (node (ref "N6") (pin "5") (pinfunction "Cathode_\"5\"_5") (pintype "passive"))
      (node (ref "U4") (pin "49") (pinfunction "HVout56/9_49") (pintype "passive"))
    )
    (net (code "73") (name "/N6_6") (class "Default")
      (node (ref "N6") (pin "6") (pinfunction "Cathode_\"6\"_6") (pintype "passive"))
      (node (ref "U4") (pin "50") (pinfunction "HVout55/10_50") (pintype "passive"))
    )
    (net (code "74") (name "/N6_7") (class "Default")
      (node (ref "N6") (pin "7") (pinfunction "Cathode_\"7\"_7") (pintype "passive"))
      (node (ref "U4") (pin "51") (pinfunction "HVout54/11_51") (pintype "passive"))
    )
    (net (code "75") (name "/N6_8") (class "Default")
      (node (ref "N6") (pin "8") (pinfunction "Cathode_\"8\"_8") (pintype "passive"))
      (node (ref "U4") (pin "52") (pinfunction "HVout53/12_52") (pintype "passive"))
    )
    (net (code "76") (name "/N6_9") (class "Default")
      (node (ref "N6") (pin "9") (pinfunction "Cathode_\"9\"_9") (pintype "passive"))
      (node (ref "U4") (pin "53") (pinfunction "HVout52/13_53") (pintype "passive"))
    )
    (net (code "77") (name "/RTC_INT{slash}SWQ") (class "Default")
      (node (ref "U5") (pin "3") (pinfunction "INT/SWQ_3") (pintype "passive"))
      (node (ref "U6") (pin "4") (pinfunction "SENSOR_VP_4") (pintype "passive"))
    )
    (net (code "78") (name "/RXD") (class "Default")
      (node (ref "J2") (pin "2") (pinfunction "TXD_2") (pintype "passive"))
      (node (ref "U6") (pin "34") (pinfunction "RXD0_34") (pintype "passive"))
    )
    (net (code "79") (name "/SCL") (class "Default")
      (node (ref "J1") (pin "3") (pinfunction "3_3") (pintype "passive"))
      (node (ref "R10") (pin "1") (pinfunction "1_1") (pintype "passive"))
      (node (ref "U5") (pin "16") (pinfunction "SCL_16") (pintype "passive"))
      (node (ref "U6") (pin "8") (pinfunction "IO32_8") (pintype "passive"))
    )
    (net (code "80") (name "/SDA") (class "Default")
      (node (ref "J1") (pin "4") (pinfunction "4_4") (pintype "passive"))
      (node (ref "R11") (pin "1") (pinfunction "1_1") (pintype "passive"))
      (node (ref "U5") (pin "15") (pinfunction "SDA_15") (pintype "passive"))
      (node (ref "U6") (pin "9") (pinfunction "IO33_9") (pintype "passive"))
    )
    (net (code "81") (name "/TXD") (class "Default")
      (node (ref "J2") (pin "3") (pinfunction "RXD_3") (pintype "passive"))
      (node (ref "U6") (pin "35") (pinfunction "TXD0_35") (pintype "passive"))
    )
    (net (code "82") (name "/touch") (class "Default")
      (node (ref "U6") (pin "13") (pinfunction "IO14_13") (pintype "passive"))
      (node (ref "touch1") (pin "1") (pinfunction "1_1") (pintype "passive"))
    )
    (net (code "83") (name "3.3V") (class "Default")
      (node (ref "C10") (pin "2") (pinfunction "2_2") (pintype "passive"))
      (node (ref "C14") (pin "2") (pinfunction "2_2") (pintype "passive"))
      (node (ref "C15") (pin "2") (pinfunction "2_2") (pintype "passive"))
      (node (ref "C7") (pin "2") (pinfunction "2_2") (pintype "passive"))
      (node (ref "Q2") (pin "2") (pinfunction "E_2") (pintype "passive"))
      (node (ref "R10") (pin "2") (pinfunction "2_2") (pintype "passive"))
      (node (ref "R11") (pin "2") (pinfunction "2_2") (pintype "passive"))
      (node (ref "R12") (pin "2") (pinfunction "2_2") (pintype "passive"))
      (node (ref "R14") (pin "2") (pinfunction "2_2") (pintype "passive"))
      (node (ref "R15") (pin "2") (pinfunction "2_2") (pintype "passive"))
      (node (ref "R21") (pin "2") (pinfunction "2_2") (pintype "passive"))
      (node (ref "R22") (pin "2") (pinfunction "2_2") (pintype "passive"))
      (node (ref "U3") (pin "2") (pinfunction "OUTPUT_2") (pintype "passive"))
      (node (ref "U3") (pin "4") (pinfunction "4_4") (pintype "passive"))
      (node (ref "U4") (pin "31") (pinfunction "~{B}L_31") (pintype "passive"))
      (node (ref "U4") (pin "32") (pinfunction "VDD_32") (pintype "passive"))
      (node (ref "U4") (pin "33") (pinfunction "DIR_33") (pintype "passive"))
      (node (ref "U5") (pin "2") (pinfunction "VCC_2") (pintype "passive"))
      (node (ref "U6") (pin "2") (pinfunction "3V3_2") (pintype "passive"))
    )
    (net (code "84") (name "GND") (class "Default")
      (node (ref "B1") (pin "2") (pinfunction "-_2") (pintype "passive"))
      (node (ref "BT1") (pin "2") (pinfunction "-_2") (pintype "passive"))
      (node (ref "C10") (pin "1") (pinfunction "1_1") (pintype "passive"))
      (node (ref "C11") (pin "1") (pinfunction "1_1") (pintype "passive"))
      (node (ref "C12") (pin "1") (pinfunction "1_1") (pintype "passive"))
      (node (ref "C13") (pin "1") (pinfunction "1_1") (pintype "passive"))
      (node (ref "C14") (pin "1") (pinfunction "1_1") (pintype "passive"))
      (node (ref "C15") (pin "1") (pinfunction "1_1") (pintype "passive"))
      (node (ref "C16") (pin "1") (pinfunction "1_1") (pintype "passive"))
      (node (ref "C17") (pin "1") (pinfunction "1_1") (pintype "passive"))
      (node (ref "C18") (pin "1") (pinfunction "1_1") (pintype "passive"))
      (node (ref "C19") (pin "2") (pinfunction "2_2") (pintype "passive"))
      (node (ref "C20") (pin "1") (pinfunction "1_1") (pintype "passive"))
      (node (ref "C6") (pin "1") (pinfunction "1_1") (pintype "passive"))
      (node (ref "C7") (pin "1") (pinfunction "1_1") (pintype "passive"))
      (node (ref "D2") (pin "2") (pinfunction "K_2") (pintype "passive"))
      (node (ref "D3") (pin "2") (pinfunction "2_2") (pintype "passive"))
      (node (ref "IR1") (pin "2") (pinfunction "GND_2") (pintype "passive"))
      (node (ref "J1") (pin "1") (pinfunction "1_1") (pintype "passive"))
      (node (ref "J2") (pin "1") (pinfunction "GND_1") (pintype "passive"))
      (node (ref "LED1") (pin "2") (pinfunction "2_2") (pintype "passive"))
      (node (ref "Q3") (pin "2") (pinfunction "E_2") (pintype "passive"))
      (node (ref "Q5") (pin "2") (pinfunction "E_2") (pintype "passive"))
      (node (ref "R2") (pin "1") (pinfunction "1_1") (pintype "passive"))
      (node (ref "R7") (pin "1") (pinfunction "1_1") (pintype "passive"))
      (node (ref "RST1") (pin "1") (pinfunction "A_1") (pintype "passive"))
      (node (ref "RST1") (pin "2") (pinfunction "B_2") (pintype "passive"))
      (node (ref "RST2") (pin "1") (pinfunction "A_1") (pintype "passive"))
      (node (ref "RST2") (pin "2") (pinfunction "B_2") (pintype "passive"))
      (node (ref "SW1") (pin "4") (pinfunction "4_4") (pintype "passive"))
      (node (ref "SW1") (pin "5") (pinfunction "5_5") (pintype "passive"))
      (node (ref "U2") (pin "1") (pinfunction "GND_1") (pintype "passive"))
      (node (ref "U2") (pin "2") (pinfunction "GND_2") (pintype "passive"))
      (node (ref "U2") (pin "3") (pinfunction "GND_3") (pintype "passive"))
      (node (ref "U2") (pin "4") (pinfunction "GND_4") (pintype "passive"))
      (node (ref "U2") (pin "A12") (pinfunction "GND_A12") (pintype "passive"))
      (node (ref "U2") (pin "B12") (pinfunction "GND_B12") (pintype "passive"))
      (node (ref "U3") (pin "1") (pinfunction "GND_1") (pintype "passive"))
      (node (ref "U4") (pin "34") (pinfunction "GND_34") (pintype "passive"))
      (node (ref "U5") (pin "10") (pinfunction "NC_10") (pintype "passive"))
      (node (ref "U5") (pin "11") (pinfunction "NC_11") (pintype "passive"))
      (node (ref "U5") (pin "12") (pinfunction "NC_12") (pintype "passive"))
      (node (ref "U5") (pin "13") (pinfunction "GND_13") (pintype "passive"))
      (node (ref "U5") (pin "5") (pinfunction "NC_5") (pintype "passive"))
      (node (ref "U5") (pin "6") (pinfunction "NC_6") (pintype "passive"))
      (node (ref "U5") (pin "7") (pinfunction "NC_7") (pintype "passive"))
      (node (ref "U5") (pin "8") (pinfunction "NC_8") (pintype "passive"))
      (node (ref "U5") (pin "9") (pinfunction "NC_9") (pintype "passive"))
      (node (ref "U6") (pin "1") (pinfunction "GND_1") (pintype "passive"))
      (node (ref "U6") (pin "15") (pinfunction "GND_15") (pintype "passive"))
      (node (ref "U6") (pin "38") (pinfunction "GND_38") (pintype "passive"))
      (node (ref "U6") (pin "39") (pinfunction "GND_39") (pintype "passive"))
      (node (ref "W1") (pin "3") (pinfunction "VSS_3") (pintype "passive"))
      (node (ref "W2") (pin "3") (pinfunction "VSS_3") (pintype "passive"))
      (node (ref "W3") (pin "3") (pinfunction "VSS_3") (pintype "passive"))
      (node (ref "W4") (pin "3") (pinfunction "VSS_3") (pintype "passive"))
      (node (ref "W5") (pin "3") (pinfunction "VSS_3") (pintype "passive"))
      (node (ref "W6") (pin "3") (pinfunction "VSS_3") (pintype "passive"))
    )
    (net (code "85") (name "HV") (class "Default")
      (node (ref "C5") (pin "2") (pinfunction "2_2") (pintype "passive"))
      (node (ref "D1") (pin "1") (pinfunction "1_1") (pintype "passive"))
      (node (ref "R16") (pin "1") (pinfunction "1_1") (pintype "passive"))
      (node (ref "R19") (pin "2") (pinfunction "2_2") (pintype "passive"))
      (node (ref "R20") (pin "2") (pinfunction "2_2") (pintype "passive"))
      (node (ref "R25") (pin "2") (pinfunction "2_2") (pintype "passive"))
      (node (ref "R26") (pin "2") (pinfunction "2_2") (pintype "passive"))
      (node (ref "R27") (pin "1") (pinfunction "1_1") (pintype "passive"))
      (node (ref "R28") (pin "1") (pinfunction "1_1") (pintype "passive"))
      (node (ref "R29") (pin "1") (pinfunction "1_1") (pintype "passive"))
      (node (ref "R30") (pin "1") (pinfunction "1_1") (pintype "passive"))
      (node (ref "R31") (pin "1") (pinfunction "1_1") (pintype "passive"))
      (node (ref "R32") (pin "1") (pinfunction "1_1") (pintype "passive"))
      (node (ref "R4") (pin "2") (pinfunction "2_2") (pintype "passive"))
      (node (ref "R5") (pin "2") (pinfunction "2_2") (pintype "passive"))
    )
    (net (code "86") (name "HVGND") (class "Default")
      (node (ref "C1") (pin "2") (pinfunction "2_2") (pintype "passive"))
      (node (ref "C2") (pin "2") (pinfunction "2_2") (pintype "passive"))
      (node (ref "C3") (pin "2") (pinfunction "2_2") (pintype "passive"))
      (node (ref "C4") (pin "1") (pinfunction "1_1") (pintype "passive"))
      (node (ref "C5") (pin "1") (pinfunction "1_1") (pintype "passive"))
      (node (ref "C8") (pin "1") (pinfunction "1_1") (pintype "passive"))
      (node (ref "C9") (pin "2") (pinfunction "2_2") (pintype "passive"))
      (node (ref "R2") (pin "2") (pinfunction "2_2") (pintype "passive"))
      (node (ref "R3") (pin "1") (pinfunction "1_1") (pintype "passive"))
      (node (ref "R6") (pin "1") (pinfunction "1_1") (pintype "passive"))
      (node (ref "R7") (pin "2") (pinfunction "2_2") (pintype "passive"))
      (node (ref "R8") (pin "1") (pinfunction "1_1") (pintype "passive"))
      (node (ref "R9") (pin "1") (pinfunction "1_1") (pintype "passive"))
      (node (ref "T1") (pin "3") (pinfunction "4_3") (pintype "passive"))
      (node (ref "U1") (pin "3") (pinfunction "GND_3") (pintype "passive"))
      (node (ref "U1") (pin "7") (pinfunction "PGND_7") (pintype "passive"))
    )
    (net (code "87") (name "Net-(B1-+)") (class "Default")
      (node (ref "B1") (pin "1") (pinfunction "+_1") (pintype "passive"))
      (node (ref "D3") (pin "1") (pinfunction "1_1") (pintype "passive"))
      (node (ref "Q2") (pin "3") (pinfunction "C_3") (pintype "passive"))
    )
    (net (code "88") (name "Net-(BT1-+)") (class "Default")
      (node (ref "BT1") (pin "1") (pinfunction "+_1") (pintype "passive"))
      (node (ref "C11") (pin "2") (pinfunction "2_2") (pintype "passive"))
      (node (ref "U5") (pin "14") (pinfunction "VBAT_14") (pintype "passive"))
    )
    (net (code "89") (name "Net-(D2-A)") (class "Default")
      (node (ref "D2") (pin "1") (pinfunction "A_1") (pintype "passive"))
      (node (ref "R16") (pin "2") (pinfunction "2_2") (pintype "passive"))
      (node (ref "U4") (pin "40") (pinfunction "VPP_40") (pintype "passive"))
    )
    (net (code "90") (name "Net-(Dot1-1-Pad2)") (class "Default")
      (node (ref "Dot1-1") (pin "2") (pinfunction "2_2") (pintype "passive"))
      (node (ref "R19") (pin "1") (pinfunction "1_1") (pintype "passive"))
    )
    (net (code "91") (name "Net-(Dot1-2-Pad2)") (class "Default")
      (node (ref "Dot1-2") (pin "2") (pinfunction "2_2") (pintype "passive"))
      (node (ref "R20") (pin "1") (pinfunction "1_1") (pintype "passive"))
    )
    (net (code "92") (name "Net-(Dot2-1-Pad2)") (class "Default")
      (node (ref "Dot2-1") (pin "2") (pinfunction "2_2") (pintype "passive"))
      (node (ref "R25") (pin "1") (pinfunction "1_1") (pintype "passive"))
    )
    (net (code "93") (name "Net-(Dot2-2-Pad2)") (class "Default")
      (node (ref "Dot2-2") (pin "2") (pinfunction "2_2") (pintype "passive"))
      (node (ref "R26") (pin "1") (pinfunction "1_1") (pintype "passive"))
    )
    (net (code "94") (name "Net-(F1-Pad1)") (class "Default")
      (node (ref "F1") (pin "1") (pinfunction "1_1") (pintype "passive"))
      (node (ref "SW1") (pin "2") (pinfunction "2_2") (pintype "passive"))
    )
    (net (code "95") (name "Net-(F1-Pad2)") (class "Default")
      (node (ref "F1") (pin "2") (pinfunction "2_2") (pintype "passive"))
      (node (ref "U2") (pin "A9") (pinfunction "VBUS_A9") (pintype "passive"))
      (node (ref "U2") (pin "B9") (pinfunction "VBUS_B9") (pintype "passive"))
    )
    (net (code "96") (name "Net-(IR1-VCC)") (class "Default")
      (node (ref "C19") (pin "1") (pinfunction "1_1") (pintype "passive"))
      (node (ref "IR1") (pin "3") (pinfunction "VCC_3") (pintype "passive"))
      (node (ref "R21") (pin "1") (pinfunction "1_1") (pintype "passive"))
    )
    (net (code "97") (name "Net-(LED1-Pad1)") (class "Default")
      (node (ref "LED1") (pin "1") (pinfunction "1_1") (pintype "passive"))
      (node (ref "R1") (pin "2") (pinfunction "2_2") (pintype "passive"))
    )
    (net (code "98") (name "Net-(N1-Anode)") (class "Default")
      (node (ref "N1") (pin "+") (pinfunction "Anode_+") (pintype "passive"))
      (node (ref "R27") (pin "2") (pinfunction "2_2") (pintype "passive"))
    )
    (net (code "99") (name "Net-(N2-Anode)") (class "Default")
      (node (ref "N2") (pin "+") (pinfunction "Anode_+") (pintype "passive"))
      (node (ref "R28") (pin "2") (pinfunction "2_2") (pintype "passive"))
    )
    (net (code "100") (name "Net-(N3-Anode)") (class "Default")
      (node (ref "N3") (pin "+") (pinfunction "Anode_+") (pintype "passive"))
      (node (ref "R29") (pin "2") (pinfunction "2_2") (pintype "passive"))
    )
    (net (code "101") (name "Net-(N4-Anode)") (class "Default")
      (node (ref "N4") (pin "+") (pinfunction "Anode_+") (pintype "passive"))
      (node (ref "R30") (pin "2") (pinfunction "2_2") (pintype "passive"))
    )
    (net (code "102") (name "Net-(N5-Anode)") (class "Default")
      (node (ref "N5") (pin "+") (pinfunction "Anode_+") (pintype "passive"))
      (node (ref "R31") (pin "2") (pinfunction "2_2") (pintype "passive"))
    )
    (net (code "103") (name "Net-(N6-Anode)") (class "Default")
      (node (ref "N6") (pin "+") (pinfunction "Anode_+") (pintype "passive"))
      (node (ref "R32") (pin "2") (pinfunction "2_2") (pintype "passive"))
    )
    (net (code "104") (name "Net-(Q1-G)") (class "Default")
      (node (ref "Q1") (pin "4") (pinfunction "G_4") (pintype "passive"))
      (node (ref "U1") (pin "8") (pinfunction "EXT_8") (pintype "passive"))
    )
    (net (code "105") (name "Net-(Q2-B)") (class "Default")
      (node (ref "Q2") (pin "1") (pinfunction "B_1") (pintype "passive"))
      (node (ref "R13") (pin "1") (pinfunction "1_1") (pintype "passive"))
    )
    (net (code "106") (name "Net-(Q3-B)") (class "Default")
      (node (ref "Q3") (pin "1") (pinfunction "B_1") (pintype "passive"))
      (node (ref "R17") (pin "1") (pinfunction "1_1") (pintype "passive"))
    )
    (net (code "107") (name "Net-(Q3-C)") (class "Default")
      (node (ref "Dot1-1") (pin "1") (pinfunction "1_1") (pintype "passive"))
      (node (ref "Dot1-2") (pin "1") (pinfunction "1_1") (pintype "passive"))
      (node (ref "Q3") (pin "3") (pinfunction "C_3") (pintype "passive"))
    )
    (net (code "108") (name "Net-(Q5-B)") (class "Default")
      (node (ref "Q5") (pin "1") (pinfunction "B_1") (pintype "passive"))
      (node (ref "R23") (pin "1") (pinfunction "1_1") (pintype "passive"))
    )
    (net (code "109") (name "Net-(Q5-C)") (class "Default")
      (node (ref "Dot2-1") (pin "1") (pinfunction "1_1") (pintype "passive"))
      (node (ref "Dot2-2") (pin "1") (pinfunction "1_1") (pintype "passive"))
      (node (ref "Q5") (pin "3") (pinfunction "C_3") (pintype "passive"))
    )
    (net (code "110") (name "Net-(T1-2)") (class "Default")
      (node (ref "Q1") (pin "5") (pinfunction "D_5") (pintype "passive"))
      (node (ref "Q1") (pin "6") (pinfunction "D_6") (pintype "passive"))
      (node (ref "Q1") (pin "7") (pinfunction "D_7") (pintype "passive"))
      (node (ref "Q1") (pin "8") (pinfunction "D_8") (pintype "passive"))
      (node (ref "Q1") (pin "9") (pinfunction "D_9") (pintype "passive"))
      (node (ref "T1") (pin "5") (pinfunction "2_5") (pintype "passive"))
    )
    (net (code "111") (name "Net-(T1-3)") (class "Default")
      (node (ref "D1") (pin "2") (pinfunction "2_2") (pintype "passive"))
      (node (ref "T1") (pin "2") (pinfunction "3_2") (pintype "passive"))
    )
    (net (code "112") (name "Net-(U1-CS+)") (class "Default")
      (node (ref "Q1") (pin "1") (pinfunction "S_1") (pintype "passive"))
      (node (ref "Q1") (pin "2") (pinfunction "S_2") (pintype "passive"))
      (node (ref "Q1") (pin "3") (pinfunction "S_3") (pintype "passive"))
      (node (ref "R8") (pin "2") (pinfunction "2_2") (pintype "passive"))
      (node (ref "U1") (pin "6") (pinfunction "CS+_6") (pintype "passive"))
    )
    (net (code "113") (name "Net-(U1-FREQ)") (class "Default")
      (node (ref "R6") (pin "2") (pinfunction "2_2") (pintype "passive"))
      (node (ref "U1") (pin "2") (pinfunction "FREQ_2") (pintype "passive"))
    )
    (net (code "114") (name "Net-(U1-LDO)") (class "Default")
      (node (ref "C4") (pin "2") (pinfunction "2_2") (pintype "passive"))
      (node (ref "U1") (pin "1") (pinfunction "LDO_1") (pintype "passive"))
    )
    (net (code "115") (name "Net-(U1-REF)") (class "Default")
      (node (ref "C8") (pin "2") (pinfunction "2_2") (pintype "passive"))
      (node (ref "U1") (pin "4") (pinfunction "REF_4") (pintype "passive"))
    )
    (net (code "116") (name "Net-(W1-DOUT)") (class "Default")
      (node (ref "W1") (pin "2") (pinfunction "DOUT_2") (pintype "passive"))
      (node (ref "W2") (pin "4") (pinfunction "DIN_4") (pintype "passive"))
    )
    (net (code "117") (name "Net-(W2-DOUT)") (class "Default")
      (node (ref "W2") (pin "2") (pinfunction "DOUT_2") (pintype "passive"))
      (node (ref "W3") (pin "4") (pinfunction "DIN_4") (pintype "passive"))
    )
    (net (code "118") (name "Net-(W3-DOUT)") (class "Default")
      (node (ref "W3") (pin "2") (pinfunction "DOUT_2") (pintype "passive"))
      (node (ref "W4") (pin "4") (pinfunction "DIN_4") (pintype "passive"))
    )
    (net (code "119") (name "Net-(W4-DOUT)") (class "Default")
      (node (ref "W4") (pin "2") (pinfunction "DOUT_2") (pintype "passive"))
      (node (ref "W5") (pin "4") (pinfunction "DIN_4") (pintype "passive"))
    )
    (net (code "120") (name "Net-(W5-DOUT)") (class "Default")
      (node (ref "W5") (pin "2") (pinfunction "DOUT_2") (pintype "passive"))
      (node (ref "W6") (pin "4") (pinfunction "DIN_4") (pintype "passive"))
    )
    (net (code "121") (name "VIN") (class "Default")
      (node (ref "C1") (pin "1") (pinfunction "1_1") (pintype "passive"))
      (node (ref "C12") (pin "2") (pinfunction "2_2") (pintype "passive"))
      (node (ref "C13") (pin "2") (pinfunction "2_2") (pintype "passive"))
      (node (ref "C16") (pin "2") (pinfunction "2_2") (pintype "passive"))
      (node (ref "C17") (pin "2") (pinfunction "2_2") (pintype "passive"))
      (node (ref "C18") (pin "2") (pinfunction "2_2") (pintype "passive"))
      (node (ref "C2") (pin "1") (pinfunction "1_1") (pintype "passive"))
      (node (ref "C20") (pin "2") (pinfunction "2_2") (pintype "passive"))
      (node (ref "C3") (pin "1") (pinfunction "1_1") (pintype "passive"))
      (node (ref "C6") (pin "2") (pinfunction "2_2") (pintype "passive"))
      (node (ref "J1") (pin "2") (pinfunction "2_2") (pintype "passive"))
      (node (ref "R1") (pin "1") (pinfunction "1_1") (pintype "passive"))
      (node (ref "SW1") (pin "1") (pinfunction "1_1") (pintype "passive"))
      (node (ref "T1") (pin "1") (pinfunction "1_1") (pintype "passive"))
      (node (ref "U1") (pin "9") (pinfunction "VCC_9") (pintype "passive"))
      (node (ref "U3") (pin "3") (pinfunction "INPUT_3") (pintype "passive"))
      (node (ref "W1") (pin "1") (pinfunction "VDD_1") (pintype "passive"))
      (node (ref "W2") (pin "1") (pinfunction "VDD_1") (pintype "passive"))
      (node (ref "W3") (pin "1") (pinfunction "VDD_1") (pintype "passive"))
      (node (ref "W4") (pin "1") (pinfunction "VDD_1") (pintype "passive"))
      (node (ref "W5") (pin "1") (pinfunction "VDD_1") (pintype "passive"))
      (node (ref "W6") (pin "1") (pinfunction "VDD_1") (pintype "passive"))
    )
    (net (code "122") (name "unconnected-(N1-Cathode_comma-PadD1)") (class "Default")
      (node (ref "N1") (pin "D1") (pinfunction "Cathode_comma_D1") (pintype "passive"))
    )
    (net (code "123") (name "unconnected-(N1-Cathode_comma-PadD2)") (class "Default")
      (node (ref "N1") (pin "D2") (pinfunction "Cathode_comma_D2") (pintype "passive"))
    )
    (net (code "124") (name "unconnected-(N2-Cathode_comma-PadD1)") (class "Default")
      (node (ref "N2") (pin "D1") (pinfunction "Cathode_comma_D1") (pintype "passive"))
    )
    (net (code "125") (name "unconnected-(N2-Cathode_comma-PadD2)") (class "Default")
      (node (ref "N2") (pin "D2") (pinfunction "Cathode_comma_D2") (pintype "passive"))
    )
    (net (code "126") (name "unconnected-(N3-Cathode_comma-PadD1)") (class "Default")
      (node (ref "N3") (pin "D1") (pinfunction "Cathode_comma_D1") (pintype "passive"))
    )
    (net (code "127") (name "unconnected-(N3-Cathode_comma-PadD2)") (class "Default")
      (node (ref "N3") (pin "D2") (pinfunction "Cathode_comma_D2") (pintype "passive"))
    )
    (net (code "128") (name "unconnected-(N4-Cathode_comma-PadD1)") (class "Default")
      (node (ref "N4") (pin "D1") (pinfunction "Cathode_comma_D1") (pintype "passive"))
    )
    (net (code "129") (name "unconnected-(N4-Cathode_comma-PadD2)") (class "Default")
      (node (ref "N4") (pin "D2") (pinfunction "Cathode_comma_D2") (pintype "passive"))
    )
    (net (code "130") (name "unconnected-(N5-Cathode_comma-PadD1)") (class "Default")
      (node (ref "N5") (pin "D1") (pinfunction "Cathode_comma_D1") (pintype "passive"))
    )
    (net (code "131") (name "unconnected-(N5-Cathode_comma-PadD2)") (class "Default")
      (node (ref "N5") (pin "D2") (pinfunction "Cathode_comma_D2") (pintype "passive"))
    )
    (net (code "132") (name "unconnected-(N6-Cathode_comma-PadD1)") (class "Default")
      (node (ref "N6") (pin "D1") (pinfunction "Cathode_comma_D1") (pintype "passive"))
    )
    (net (code "133") (name "unconnected-(N6-Cathode_comma-PadD2)") (class "Default")
      (node (ref "N6") (pin "D2") (pinfunction "Cathode_comma_D2") (pintype "passive"))
    )
    (net (code "134") (name "unconnected-(SW1-Pad3)") (class "Default")
      (node (ref "SW1") (pin "3") (pinfunction "3_3") (pintype "passive"))
    )
    (net (code "135") (name "unconnected-(U2-CC1-PadA5)") (class "Default")
      (node (ref "U2") (pin "A5") (pinfunction "CC1_A5") (pintype "passive"))
    )
    (net (code "136") (name "unconnected-(U2-CC2-PadB5)") (class "Default")
      (node (ref "U2") (pin "B5") (pinfunction "CC2_B5") (pintype "passive"))
    )
    (net (code "137") (name "unconnected-(U4-Dout1{slash}Din4(B)-Pad39)") (class "Default")
      (node (ref "U4") (pin "39") (pinfunction "Dout1/Din4(B)_39") (pintype "passive"))
    )
    (net (code "138") (name "unconnected-(U4-Dout2{slash}Din3(B)-Pad38)") (class "Default")
      (node (ref "U4") (pin "38") (pinfunction "Dout2/Din3(B)_38") (pintype "passive"))
    )
    (net (code "139") (name "unconnected-(U4-Dout3{slash}Din2(B)-Pad37)") (class "Default")
      (node (ref "U4") (pin "37") (pinfunction "Dout3/Din2(B)_37") (pintype "passive"))
    )
    (net (code "140") (name "unconnected-(U4-Dout4{slash}Din1(B)-Pad36)") (class "Default")
      (node (ref "U4") (pin "36") (pinfunction "Dout4/Din1(B)_36") (pintype "passive"))
    )
    (net (code "141") (name "unconnected-(U4-HVout61{slash}4-Pad44)") (class "Default")
      (node (ref "U4") (pin "44") (pinfunction "HVout61/4_44") (pintype "passive"))
    )
    (net (code "142") (name "unconnected-(U4-HVout62{slash}3-Pad43)") (class "Default")
      (node (ref "U4") (pin "43") (pinfunction "HVout62/3_43") (pintype "passive"))
    )
    (net (code "143") (name "unconnected-(U4-HVout63{slash}2-Pad42)") (class "Default")
      (node (ref "U4") (pin "42") (pinfunction "HVout63/2_42") (pintype "passive"))
    )
    (net (code "144") (name "unconnected-(U4-HVout64{slash}1-Pad41)") (class "Default")
      (node (ref "U4") (pin "41") (pinfunction "HVout64/1_41") (pintype "passive"))
    )
    (net (code "145") (name "unconnected-(U5-32kHz-Pad1)") (class "Default")
      (node (ref "U5") (pin "1") (pinfunction "32kHz_1") (pintype "passive"))
    )
    (net (code "146") (name "unconnected-(U5-RST-Pad4)") (class "Default")
      (node (ref "U5") (pin "4") (pinfunction "RST_4") (pintype "passive"))
    )
    (net (code "147") (name "unconnected-(U6-IO2-Pad24)") (class "Default")
      (node (ref "U6") (pin "24") (pinfunction "IO2_24") (pintype "passive"))
    )
    (net (code "148") (name "unconnected-(U6-IO5-Pad29)") (class "Default")
      (node (ref "U6") (pin "29") (pinfunction "IO5_29") (pintype "passive"))
    )
    (net (code "149") (name "unconnected-(U6-IO12-Pad14)") (class "Default")
      (node (ref "U6") (pin "14") (pinfunction "IO12_14") (pintype "passive"))
    )
    (net (code "150") (name "unconnected-(U6-IO15-Pad23)") (class "Default")
      (node (ref "U6") (pin "23") (pinfunction "IO15_23") (pintype "passive"))
    )
    (net (code "151") (name "unconnected-(U6-IO34-Pad6)") (class "Default")
      (node (ref "U6") (pin "6") (pinfunction "IO34_6") (pintype "passive"))
    )
    (net (code "152") (name "unconnected-(U6-IO35-Pad7)") (class "Default")
      (node (ref "U6") (pin "7") (pinfunction "IO35_7") (pintype "passive"))
    )
    (net (code "153") (name "unconnected-(U6-NC-Pad17)") (class "Default")
      (node (ref "U6") (pin "17") (pinfunction "NC_17") (pintype "passive"))
    )
    (net (code "154") (name "unconnected-(U6-NC-Pad18)") (class "Default")
      (node (ref "U6") (pin "18") (pinfunction "NC_18") (pintype "passive"))
    )
    (net (code "155") (name "unconnected-(U6-NC-Pad19)") (class "Default")
      (node (ref "U6") (pin "19") (pinfunction "NC_19") (pintype "passive"))
    )
    (net (code "156") (name "unconnected-(U6-NC-Pad20)") (class "Default")
      (node (ref "U6") (pin "20") (pinfunction "NC_20") (pintype "passive"))
    )
    (net (code "157") (name "unconnected-(U6-NC-Pad21)") (class "Default")
      (node (ref "U6") (pin "21") (pinfunction "NC_21") (pintype "passive"))
    )
    (net (code "158") (name "unconnected-(U6-NC-Pad22)") (class "Default")
      (node (ref "U6") (pin "22") (pinfunction "NC_22") (pintype "passive"))
    )
    (net (code "159") (name "unconnected-(U6-NC-Pad32)") (class "Default")
      (node (ref "U6") (pin "32") (pinfunction "NC_32") (pintype "passive"))
    )
    (net (code "160") (name "unconnected-(W6-DOUT-Pad2)") (class "Default")
      (node (ref "W6") (pin "2") (pinfunction "DOUT_2") (pintype "passive"))
    )
  )
)
